# 11-Ice40_FPGA.net
KiCad netlist of a schematic drawn in Altium Designer
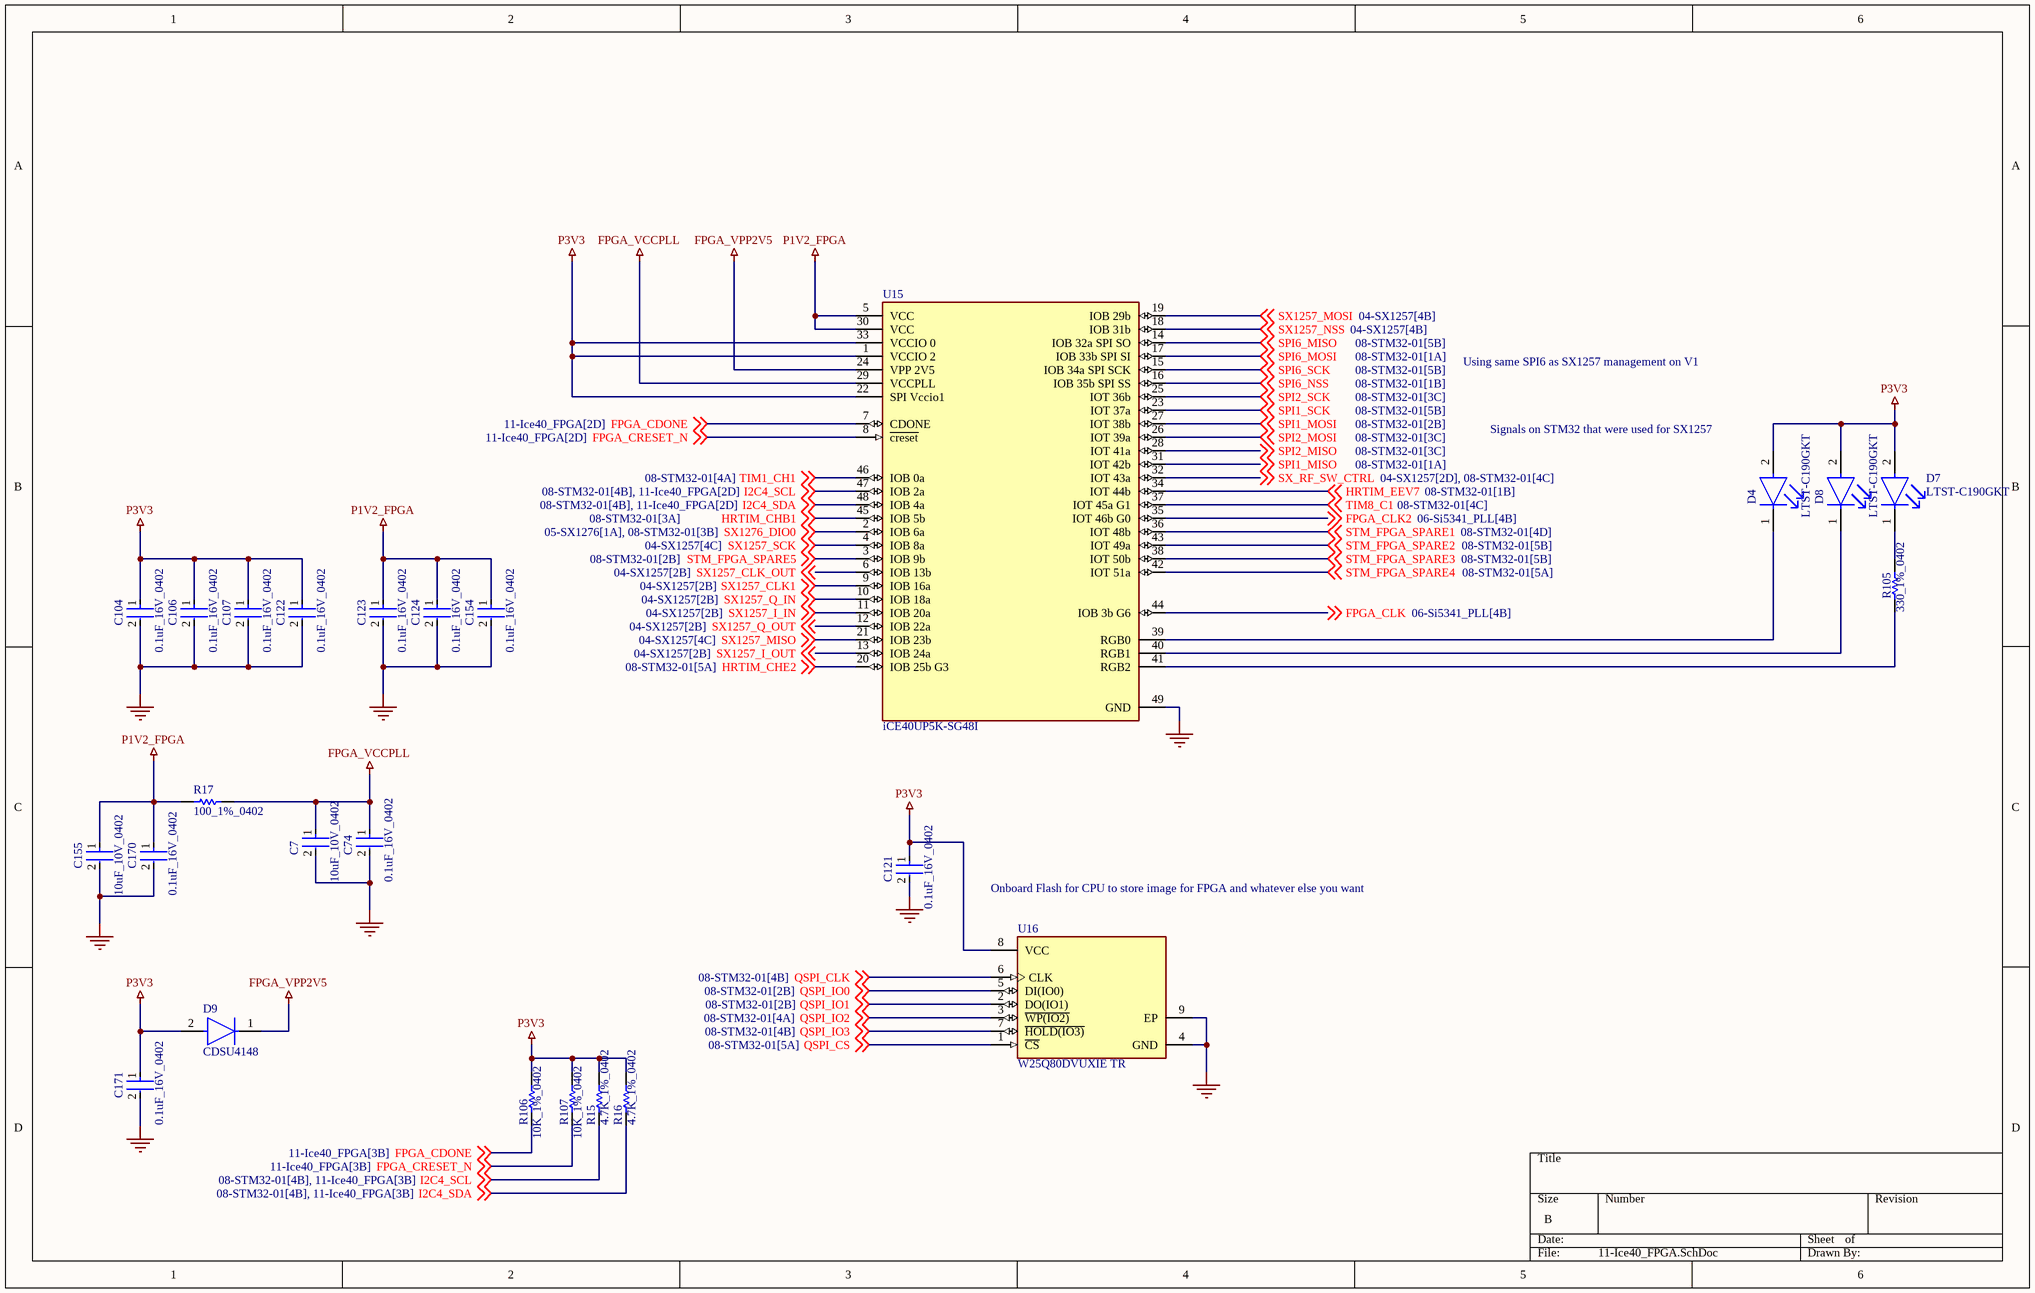
[diagram p0: 11-Ice40_FPGA.SchDoc]

(export (version "E")
  (design (tool "Eeschema 10.0.6"))
  (components
    (comp (ref "C7")
      (value "10uF_10V_0402")
      (footprint "FP-CL05A106MP5NUNC-MFG")
      (description "CAP CER 10UF 10V X5R 0402")
      (fields
        (field (name "OCTOPART") "https://octopart.com/cl05a106mp5nunc-samsung-22457395")
        (field (name "TOLERANCE") "20%")
      )
      (libsource (lib "Altium Content Vault") (part "b4654b650e69147ec39a6b967a45e02"))
    )
    (comp (ref "C74")
      (value "0.1uF_16V_0402")
      (footprint "FP-C0402-BB-MFG")
      (description "CAP CER 0.1UF 16V 5% X7R 0402")
      (fields
        (field (name "MANUFACTURER") "Kemet")
        (field (name "MANUFACTURER PART NUMBER") "C0402C104J4RACTU")
      )
      (libsource (lib "Altium Content Vault") (part "b4654b650e69147ec39a6b967a45e02"))
    )
    (comp (ref "C104")
      (value "0.1uF_16V_0402")
      (footprint "FP-C0402-BB-MFG")
      (description "CAP CER 0.1UF 16V 5% X7R 0402")
      (fields
        (field (name "MANUFACTURER") "Kemet")
        (field (name "MANUFACTURER PART NUMBER") "C0402C104J4RACTU")
      )
      (libsource (lib "Altium Content Vault") (part "b4654b650e69147ec39a6b967a45e02"))
    )
    (comp (ref "C106")
      (value "0.1uF_16V_0402")
      (footprint "FP-C0402-BB-MFG")
      (description "CAP CER 0.1UF 16V 5% X7R 0402")
      (fields
        (field (name "MANUFACTURER") "Kemet")
        (field (name "MANUFACTURER PART NUMBER") "C0402C104J4RACTU")
      )
      (libsource (lib "Altium Content Vault") (part "b4654b650e69147ec39a6b967a45e02"))
    )
    (comp (ref "C107")
      (value "0.1uF_16V_0402")
      (footprint "FP-C0402-BB-MFG")
      (description "CAP CER 0.1UF 16V 5% X7R 0402")
      (fields
        (field (name "MANUFACTURER") "Kemet")
        (field (name "MANUFACTURER PART NUMBER") "C0402C104J4RACTU")
      )
      (libsource (lib "Altium Content Vault") (part "b4654b650e69147ec39a6b967a45e02"))
    )
    (comp (ref "C121")
      (value "0.1uF_16V_0402")
      (footprint "FP-C0402-BB-MFG")
      (description "CAP CER 0.1UF 16V 5% X7R 0402")
      (fields
        (field (name "MANUFACTURER") "Kemet")
        (field (name "MANUFACTURER PART NUMBER") "C0402C104J4RACTU")
      )
      (libsource (lib "Altium Content Vault") (part "b4654b650e69147ec39a6b967a45e02"))
    )
    (comp (ref "C122")
      (value "0.1uF_16V_0402")
      (footprint "FP-C0402-BB-MFG")
      (description "CAP CER 0.1UF 16V 5% X7R 0402")
      (fields
        (field (name "MANUFACTURER") "Kemet")
        (field (name "MANUFACTURER PART NUMBER") "C0402C104J4RACTU")
      )
      (libsource (lib "Altium Content Vault") (part "b4654b650e69147ec39a6b967a45e02"))
    )
    (comp (ref "C123")
      (value "0.1uF_16V_0402")
      (footprint "FP-C0402-BB-MFG")
      (description "CAP CER 0.1UF 16V 5% X7R 0402")
      (fields
        (field (name "MANUFACTURER") "Kemet")
        (field (name "MANUFACTURER PART NUMBER") "C0402C104J4RACTU")
      )
      (libsource (lib "Altium Content Vault") (part "b4654b650e69147ec39a6b967a45e02"))
    )
    (comp (ref "C124")
      (value "0.1uF_16V_0402")
      (footprint "FP-C0402-BB-MFG")
      (description "CAP CER 0.1UF 16V 5% X7R 0402")
      (fields
        (field (name "MANUFACTURER") "Kemet")
        (field (name "MANUFACTURER PART NUMBER") "C0402C104J4RACTU")
      )
      (libsource (lib "Altium Content Vault") (part "b4654b650e69147ec39a6b967a45e02"))
    )
    (comp (ref "C154")
      (value "0.1uF_16V_0402")
      (footprint "FP-C0402-BB-MFG")
      (description "CAP CER 0.1UF 16V 5% X7R 0402")
      (fields
        (field (name "MANUFACTURER") "Kemet")
        (field (name "MANUFACTURER PART NUMBER") "C0402C104J4RACTU")
      )
      (libsource (lib "Altium Content Vault") (part "b4654b650e69147ec39a6b967a45e02"))
    )
    (comp (ref "C155")
      (value "10uF_10V_0402")
      (footprint "FP-CL05A106MP5NUNC-MFG")
      (description "CAP CER 10UF 10V X5R 0402")
      (fields
        (field (name "OCTOPART") "https://octopart.com/cl05a106mp5nunc-samsung-22457395")
        (field (name "TOLERANCE") "20%")
      )
      (libsource (lib "Altium Content Vault") (part "b4654b650e69147ec39a6b967a45e02"))
    )
    (comp (ref "C170")
      (value "0.1uF_16V_0402")
      (footprint "FP-C0402-BB-MFG")
      (description "CAP CER 0.1UF 16V 5% X7R 0402")
      (fields
        (field (name "MANUFACTURER") "Kemet")
        (field (name "MANUFACTURER PART NUMBER") "C0402C104J4RACTU")
      )
      (libsource (lib "Altium Content Vault") (part "b4654b650e69147ec39a6b967a45e02"))
    )
    (comp (ref "C171")
      (value "0.1uF_16V_0402")
      (footprint "FP-C0402-BB-MFG")
      (description "CAP CER 0.1UF 16V 5% X7R 0402")
      (fields
        (field (name "MANUFACTURER") "Kemet")
        (field (name "MANUFACTURER PART NUMBER") "C0402C104J4RACTU")
      )
      (libsource (lib "Altium Content Vault") (part "b4654b650e69147ec39a6b967a45e02"))
    )
    (comp (ref "D4")
      (value "LTST-C190GKT")
      (footprint "FP-LTST-C190GKT-MFG")
      (description "LED GREEN CLEAR CHIP SMD")
      (fields (field (name "VOLTAGE") "2V"))
      (libsource (lib "Altium Content Vault") (part "8706943c75ba83719d021d2fdc84c58"))
    )
    (comp (ref "D7")
      (value "LTST-C190GKT")
      (footprint "FP-LTST-C190GKT-MFG")
      (description "LED GREEN CLEAR CHIP SMD")
      (fields (field (name "VOLTAGE") "2V"))
      (libsource (lib "Altium Content Vault") (part "8706943c75ba83719d021d2fdc84c58"))
    )
    (comp (ref "D8")
      (value "LTST-C190GKT")
      (footprint "FP-LTST-C190GKT-MFG")
      (description "LED GREEN CLEAR CHIP SMD")
      (fields (field (name "VOLTAGE") "2V"))
      (libsource (lib "Altium Content Vault") (part "8706943c75ba83719d021d2fdc84c58"))
    )
    (comp (ref "D9")
      (value "CDSU4148")
      (footprint "FP-0603-SOD-523F-MFG")
      (description "DIODE GEN PURP 75V 150MA 0603")
      (libsource (lib "Altium Content Vault") (part "d7152d700b627762746794eb795d46e"))
    )
    (comp (ref "R15")
      (value "4.7K_1%_0402")
      (footprint "RESC1005X40X25NL10T10")
      (fields (field (name "MANUFACTURER") "Bourns") (field (name "PART NUMBER") "CR0402-FX-4701GLF"))
      (libsource (lib "Altium Content Vault") (part "RES"))
    )
    (comp (ref "R16")
      (value "4.7K_1%_0402")
      (footprint "RESC1005X40X25NL10T10")
      (fields (field (name "MANUFACTURER") "Bourns") (field (name "PART NUMBER") "CR0402-FX-4701GLF"))
      (libsource (lib "Altium Content Vault") (part "RES"))
    )
    (comp (ref "R17")
      (value "100_1%_0402")
      (footprint "RESC1005X40X25LL05T05")
      (description "Chip Resistor, 100 Ohm, +/- 1%, 100 mW, -55 to 155 degC, 0402 (1005 Metric), RoHS, Tape and Reel")
      (fields (field (name "MANUFACTURER") "Basic Passives") (field (name "TOLERANCE") "1%"))
      (libsource (lib "Altium Content Vault") (part "RES-2"))
    )
    (comp (ref "R105")
      (value "330_1%_0402")
      (footprint "RESC1005X40X25NL10T10")
      (fields (field (name "MANUFACTURER") "Panasonic") (field (name "PART NUMBER") "ERA-2AED331X"))
      (libsource (lib "Altium Content Vault") (part "RES"))
    )
    (comp (ref "R106")
      (value "10K_1%_0402")
      (footprint "RESC1005X40X25NL10T10")
      (fields (field (name "MANUFACTURER") "Bourns") (field (name "PART NUMBER") "CR0402-FX-1002GLF"))
      (libsource (lib "Altium Content Vault") (part "RES"))
    )
    (comp (ref "R107")
      (value "10K_1%_0402")
      (footprint "RESC1005X40X25NL10T10")
      (fields (field (name "MANUFACTURER") "Bourns") (field (name "PART NUMBER") "CR0402-FX-1002GLF"))
      (libsource (lib "Altium Content Vault") (part "RES"))
    )
    (comp (ref "U15")
      (value "iCE40UP5K-SG48I")
      (footprint "FP-QFN-48-IPC_C")
      (description "ICE40-ULTRAPLUS, 5280 LUTS, 1.2V")
      (fields
        (field (name "MANUFACTURER") "Lattice")
        (field (name "OCTOPART") "https://octopart.com/ice40up5k-sg48i-lattice+semiconductor-87369311")
      )
      (libsource (lib "Altium Content Vault") (part "90c839ece6b9b86f6dd6a74a4566a88"))
    )
    (comp (ref "U16")
      (value "W25Q80DVUXIE TR")
      (footprint "FP-UX-MFG")
      (description "IC FLASH 8M SPI 104MHZ 8USON")
      (libsource (lib "Altium Content Vault") (part "b92c346eb8c41a87421d2bcd0997ded"))
    )
  )
  (nets
    (net (code "1") (name "FPGA_CDONE") (class "Default")
      (node (ref "R106") (pin "1") (pinfunction "1_1") (pintype "passive"))
      (node (ref "U15") (pin "7") (pinfunction "CDONE_7") (pintype "bidirectional"))
    )
    (net (code "2") (name "FPGA_CLK") (class "Default")
      (node (ref "U15") (pin "44") (pinfunction "IOB_3b_G6_44") (pintype "bidirectional"))
    )
    (net (code "3") (name "FPGA_CLK2") (class "Default")
      (node (ref "U15") (pin "35") (pinfunction "IOT_46b_G0_35") (pintype "bidirectional"))
    )
    (net (code "4") (name "FPGA_CRESET_N") (class "Default")
      (node (ref "R107") (pin "1") (pinfunction "1_1") (pintype "passive"))
      (node (ref "U15") (pin "8") (pinfunction "~{creset}_8") (pintype "input"))
    )
    (net (code "5") (name "FPGA_VCCPLL") (class "Default")
      (node (ref "C7") (pin "1") (pinfunction "1_1") (pintype "passive"))
      (node (ref "C74") (pin "1") (pinfunction "1_1") (pintype "passive"))
      (node (ref "R17") (pin "2") (pinfunction "2_2") (pintype "passive"))
      (node (ref "U15") (pin "29") (pinfunction "VCCPLL_29") (pintype "power_in"))
    )
    (net (code "6") (name "FPGA_VPP2V5") (class "Default")
      (node (ref "D9") (pin "1") (pinfunction "C_1") (pintype "passive"))
      (node (ref "U15") (pin "24") (pinfunction "VPP_2V5_24") (pintype "power_in"))
    )
    (net (code "7") (name "GND") (class "Default")
      (node (ref "C104") (pin "2") (pinfunction "2_2") (pintype "passive"))
      (node (ref "C106") (pin "2") (pinfunction "2_2") (pintype "passive"))
      (node (ref "C107") (pin "2") (pinfunction "2_2") (pintype "passive"))
      (node (ref "C121") (pin "2") (pinfunction "2_2") (pintype "passive"))
      (node (ref "C122") (pin "2") (pinfunction "2_2") (pintype "passive"))
      (node (ref "C123") (pin "2") (pinfunction "2_2") (pintype "passive"))
      (node (ref "C124") (pin "2") (pinfunction "2_2") (pintype "passive"))
      (node (ref "C154") (pin "2") (pinfunction "2_2") (pintype "passive"))
      (node (ref "C155") (pin "2") (pinfunction "2_2") (pintype "passive"))
      (node (ref "C170") (pin "2") (pinfunction "2_2") (pintype "passive"))
      (node (ref "C171") (pin "2") (pinfunction "2_2") (pintype "passive"))
      (node (ref "C7") (pin "2") (pinfunction "2_2") (pintype "passive"))
      (node (ref "C74") (pin "2") (pinfunction "2_2") (pintype "passive"))
      (node (ref "U15") (pin "49") (pinfunction "GND_49") (pintype "power_in"))
      (node (ref "U16") (pin "4") (pinfunction "GND_4") (pintype "power_in"))
      (node (ref "U16") (pin "9") (pinfunction "EP_9") (pintype "passive"))
    )
    (net (code "8") (name "HRTIM_CHB1") (class "Default")
      (node (ref "U15") (pin "45") (pinfunction "IOB_5b_45") (pintype "bidirectional"))
    )
    (net (code "9") (name "HRTIM_CHE2") (class "Default")
      (node (ref "U15") (pin "20") (pinfunction "IOB_25b_G3_20") (pintype "bidirectional"))
    )
    (net (code "10") (name "HRTIM_EEV7") (class "Default")
      (node (ref "U15") (pin "34") (pinfunction "IOT_44b_34") (pintype "bidirectional"))
    )
    (net (code "11") (name "I2C4_SCL") (class "Default")
      (node (ref "R15") (pin "1") (pinfunction "1_1") (pintype "passive"))
      (node (ref "U15") (pin "47") (pinfunction "IOB_2a_47") (pintype "bidirectional"))
    )
    (net (code "12") (name "I2C4_SDA") (class "Default")
      (node (ref "R16") (pin "1") (pinfunction "1_1") (pintype "passive"))
      (node (ref "U15") (pin "48") (pinfunction "IOB_4a_48") (pintype "bidirectional"))
    )
    (net (code "13") (name "Net-(D4-C)") (class "Default")
      (node (ref "D4") (pin "1") (pinfunction "C_1") (pintype "passive"))
      (node (ref "U15") (pin "39") (pinfunction "RGB0_39") (pintype "open_collector"))
    )
    (net (code "14") (name "Net-(D7-C)") (class "Default")
      (node (ref "D7") (pin "1") (pinfunction "C_1") (pintype "passive"))
      (node (ref "R105") (pin "2") (pinfunction "2_2") (pintype "passive"))
    )
    (net (code "15") (name "Net-(D8-C)") (class "Default")
      (node (ref "D8") (pin "1") (pinfunction "C_1") (pintype "passive"))
      (node (ref "U15") (pin "40") (pinfunction "RGB1_40") (pintype "open_collector"))
    )
    (net (code "16") (name "Net-(U15-RGB2)") (class "Default")
      (node (ref "R105") (pin "1") (pinfunction "1_1") (pintype "passive"))
      (node (ref "U15") (pin "41") (pinfunction "RGB2_41") (pintype "open_collector"))
    )
    (net (code "17") (name "P1V2_FPGA") (class "Default")
      (node (ref "C123") (pin "1") (pinfunction "1_1") (pintype "passive"))
      (node (ref "C124") (pin "1") (pinfunction "1_1") (pintype "passive"))
      (node (ref "C154") (pin "1") (pinfunction "1_1") (pintype "passive"))
      (node (ref "C155") (pin "1") (pinfunction "1_1") (pintype "passive"))
      (node (ref "C170") (pin "1") (pinfunction "1_1") (pintype "passive"))
      (node (ref "R17") (pin "1") (pinfunction "1_1") (pintype "passive"))
      (node (ref "U15") (pin "30") (pinfunction "VCC_30") (pintype "power_in"))
      (node (ref "U15") (pin "5") (pinfunction "VCC_5") (pintype "power_in"))
    )
    (net (code "18") (name "P3V3") (class "Default")
      (node (ref "C104") (pin "1") (pinfunction "1_1") (pintype "passive"))
      (node (ref "C106") (pin "1") (pinfunction "1_1") (pintype "passive"))
      (node (ref "C107") (pin "1") (pinfunction "1_1") (pintype "passive"))
      (node (ref "C121") (pin "1") (pinfunction "1_1") (pintype "passive"))
      (node (ref "C122") (pin "1") (pinfunction "1_1") (pintype "passive"))
      (node (ref "C171") (pin "1") (pinfunction "1_1") (pintype "passive"))
      (node (ref "D4") (pin "2") (pinfunction "A_2") (pintype "passive"))
      (node (ref "D7") (pin "2") (pinfunction "A_2") (pintype "passive"))
      (node (ref "D8") (pin "2") (pinfunction "A_2") (pintype "passive"))
      (node (ref "D9") (pin "2") (pinfunction "A_2") (pintype "passive"))
      (node (ref "R106") (pin "2") (pinfunction "2_2") (pintype "passive"))
      (node (ref "R107") (pin "2") (pinfunction "2_2") (pintype "passive"))
      (node (ref "R15") (pin "2") (pinfunction "2_2") (pintype "passive"))
      (node (ref "R16") (pin "2") (pinfunction "2_2") (pintype "passive"))
      (node (ref "U15") (pin "1") (pinfunction "VCCIO_2_1") (pintype "power_in"))
      (node (ref "U15") (pin "22") (pinfunction "SPI_Vccio1_22") (pintype "power_in"))
      (node (ref "U15") (pin "33") (pinfunction "VCCIO_0_33") (pintype "power_in"))
      (node (ref "U16") (pin "8") (pinfunction "VCC_8") (pintype "power_in"))
    )
    (net (code "19") (name "QSPI_CLK") (class "Default")
      (node (ref "U16") (pin "6") (pinfunction "CLK_6") (pintype "input"))
    )
    (net (code "20") (name "QSPI_CS") (class "Default")
      (node (ref "U16") (pin "1") (pinfunction "~{CS}_1") (pintype "input"))
    )
    (net (code "21") (name "QSPI_IO0") (class "Default")
      (node (ref "U16") (pin "5") (pinfunction "DI(IO0)_5") (pintype "bidirectional"))
    )
    (net (code "22") (name "QSPI_IO1") (class "Default")
      (node (ref "U16") (pin "2") (pinfunction "DO(IO1)_2") (pintype "bidirectional"))
    )
    (net (code "23") (name "QSPI_IO2") (class "Default")
      (node (ref "U16") (pin "3") (pinfunction "~{WP(IO2)}_3") (pintype "bidirectional"))
    )
    (net (code "24") (name "QSPI_IO3") (class "Default")
      (node (ref "U16") (pin "7") (pinfunction "~{HOLD(IO3)}_7") (pintype "bidirectional"))
    )
    (net (code "25") (name "SPI1_MISO") (class "Default")
      (node (ref "U15") (pin "31") (pinfunction "IOT_42b_31") (pintype "bidirectional"))
    )
    (net (code "26") (name "SPI1_MOSI") (class "Default")
      (node (ref "U15") (pin "27") (pinfunction "IOT_38b_27") (pintype "bidirectional"))
    )
    (net (code "27") (name "SPI1_SCK") (class "Default")
      (node (ref "U15") (pin "23") (pinfunction "IOT_37a_23") (pintype "bidirectional"))
    )
    (net (code "28") (name "SPI2_MISO") (class "Default")
      (node (ref "U15") (pin "28") (pinfunction "IOT_41a_28") (pintype "bidirectional"))
    )
    (net (code "29") (name "SPI2_MOSI") (class "Default")
      (node (ref "U15") (pin "26") (pinfunction "IOT_39a_26") (pintype "bidirectional"))
    )
    (net (code "30") (name "SPI2_SCK") (class "Default")
      (node (ref "U15") (pin "25") (pinfunction "IOT_36b_25") (pintype "bidirectional"))
    )
    (net (code "31") (name "SPI6_MISO") (class "Default")
      (node (ref "U15") (pin "14") (pinfunction "IOB_32a_SPI_SO_14") (pintype "bidirectional"))
    )
    (net (code "32") (name "SPI6_MOSI") (class "Default")
      (node (ref "U15") (pin "17") (pinfunction "IOB_33b_SPI_SI_17") (pintype "bidirectional"))
    )
    (net (code "33") (name "SPI6_NSS") (class "Default")
      (node (ref "U15") (pin "16") (pinfunction "IOB_35b_SPI_SS_16") (pintype "bidirectional"))
    )
    (net (code "34") (name "SPI6_SCK") (class "Default")
      (node (ref "U15") (pin "15") (pinfunction "IOB_34a_SPI_SCK_15") (pintype "bidirectional"))
    )
    (net (code "35") (name "STM_FPGA_SPARE1") (class "Default")
      (node (ref "U15") (pin "36") (pinfunction "IOT_48b_36") (pintype "bidirectional"))
    )
    (net (code "36") (name "STM_FPGA_SPARE2") (class "Default")
      (node (ref "U15") (pin "43") (pinfunction "IOT_49a_43") (pintype "bidirectional"))
    )
    (net (code "37") (name "STM_FPGA_SPARE3") (class "Default")
      (node (ref "U15") (pin "38") (pinfunction "IOT_50b_38") (pintype "bidirectional"))
    )
    (net (code "38") (name "STM_FPGA_SPARE4") (class "Default")
      (node (ref "U15") (pin "42") (pinfunction "IOT_51a_42") (pintype "bidirectional"))
    )
    (net (code "39") (name "STM_FPGA_SPARE5") (class "Default")
      (node (ref "U15") (pin "3") (pinfunction "IOB_9b_3") (pintype "bidirectional"))
    )
    (net (code "40") (name "SX1257_CLK1") (class "Default")
      (node (ref "U15") (pin "9") (pinfunction "IOB_16a_9") (pintype "bidirectional"))
    )
    (net (code "41") (name "SX1257_CLK_OUT") (class "Default")
      (node (ref "U15") (pin "6") (pinfunction "IOB_13b_6") (pintype "bidirectional"))
    )
    (net (code "42") (name "SX1257_I_IN") (class "Default")
      (node (ref "U15") (pin "11") (pinfunction "IOB_20a_11") (pintype "bidirectional"))
    )
    (net (code "43") (name "SX1257_I_OUT") (class "Default")
      (node (ref "U15") (pin "13") (pinfunction "IOB_24a_13") (pintype "bidirectional"))
    )
    (net (code "44") (name "SX1257_MISO") (class "Default")
      (node (ref "U15") (pin "21") (pinfunction "IOB_23b_21") (pintype "bidirectional"))
    )
    (net (code "45") (name "SX1257_MOSI") (class "Default")
      (node (ref "U15") (pin "19") (pinfunction "IOB_29b_19") (pintype "bidirectional"))
    )
    (net (code "46") (name "SX1257_NSS") (class "Default")
      (node (ref "U15") (pin "18") (pinfunction "IOB_31b_18") (pintype "bidirectional"))
    )
    (net (code "47") (name "SX1257_Q_IN") (class "Default")
      (node (ref "U15") (pin "10") (pinfunction "IOB_18a_10") (pintype "bidirectional"))
    )
    (net (code "48") (name "SX1257_Q_OUT") (class "Default")
      (node (ref "U15") (pin "12") (pinfunction "IOB_22a_12") (pintype "bidirectional"))
    )
    (net (code "49") (name "SX1257_SCK") (class "Default")
      (node (ref "U15") (pin "4") (pinfunction "IOB_8a_4") (pintype "bidirectional"))
    )
    (net (code "50") (name "SX1276_DIO0") (class "Default")
      (node (ref "U15") (pin "2") (pinfunction "IOB_6a_2") (pintype "bidirectional"))
    )
    (net (code "51") (name "SX_RF_SW_CTRL") (class "Default")
      (node (ref "U15") (pin "32") (pinfunction "IOT_43a_32") (pintype "bidirectional"))
    )
    (net (code "52") (name "TIM1_CH1") (class "Default")
      (node (ref "U15") (pin "46") (pinfunction "IOB_0a_46") (pintype "bidirectional"))
    )
    (net (code "53") (name "TIM8_C1") (class "Default")
      (node (ref "U15") (pin "37") (pinfunction "IOT_45a_G1_37") (pintype "bidirectional"))
    )
  )
)
